# MouseGoggles_Hat-1-9.net
KiCad netlist of a schematic drawn in EAGLE
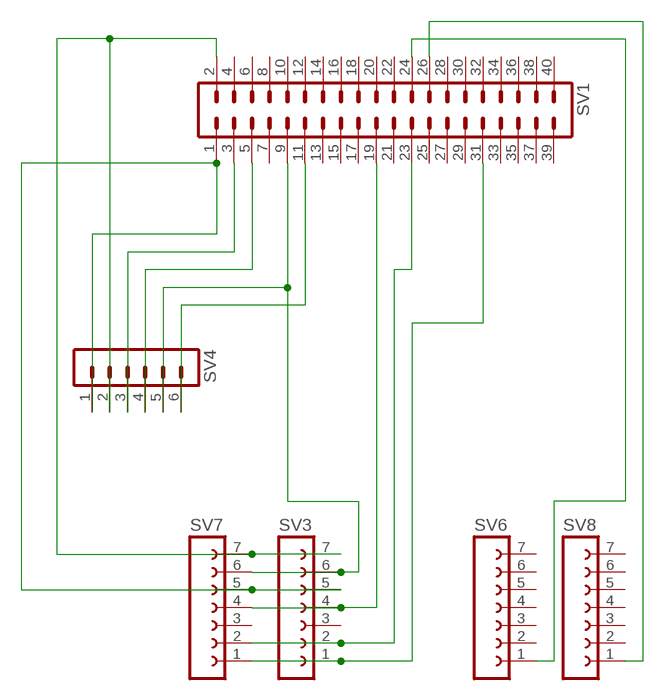
[diagram p0: schematic, sheet 1]

(export (version "E")
  (design (tool "Eeschema 10.0.6"))
  (components
    (comp (ref "SV1")
      (value "MA20-2")
      (footprint "eagle-import:MA20-2")
      (libsource (lib "eagle-import") (part "MA20-2"))
    )
    (comp (ref "SV3")
      (value "FE07-1")
      (footprint "eagle-import:FE07")
      (libsource (lib "eagle-import") (part "FE07-1"))
    )
    (comp (ref "SV4")
      (value "MA06-1")
      (footprint "eagle-import:MA06-1")
      (libsource (lib "eagle-import") (part "MA06-1"))
    )
    (comp (ref "SV6")
      (value "FE07-1")
      (footprint "eagle-import:FE07")
      (libsource (lib "eagle-import") (part "FE07-1"))
    )
    (comp (ref "SV7")
      (value "FE07-1")
      (footprint "eagle-import:FE07")
      (libsource (lib "eagle-import") (part "FE07-1"))
    )
    (comp (ref "SV8")
      (value "FE07-1")
      (footprint "eagle-import:FE07")
      (libsource (lib "eagle-import") (part "FE07-1"))
    )
  )
  (nets
    (net (code "1") (name "Net-(SV1-Pad1)") (class "Default")
      (node (ref "SV1") (pin "1") (pinfunction "1_1") (pintype "passive"))
      (node (ref "SV3") (pin "5") (pinfunction "5_5") (pintype "passive"))
      (node (ref "SV4") (pin "1") (pinfunction "1_1") (pintype "passive"))
      (node (ref "SV7") (pin "5") (pinfunction "5_5") (pintype "passive"))
    )
    (net (code "2") (name "Net-(SV1-Pad2)") (class "Default")
      (node (ref "SV1") (pin "2") (pinfunction "2_2") (pintype "passive"))
      (node (ref "SV3") (pin "7") (pinfunction "7_7") (pintype "passive"))
      (node (ref "SV4") (pin "2") (pinfunction "2_2") (pintype "passive"))
      (node (ref "SV7") (pin "7") (pinfunction "7_7") (pintype "passive"))
    )
    (net (code "3") (name "Net-(SV1-Pad3)") (class "Default")
      (node (ref "SV1") (pin "3") (pinfunction "3_3") (pintype "passive"))
      (node (ref "SV4") (pin "3") (pinfunction "3_3") (pintype "passive"))
    )
    (net (code "4") (name "Net-(SV1-Pad5)") (class "Default")
      (node (ref "SV1") (pin "5") (pinfunction "5_5") (pintype "passive"))
      (node (ref "SV4") (pin "4") (pinfunction "4_4") (pintype "passive"))
    )
    (net (code "5") (name "Net-(SV1-Pad9)") (class "Default")
      (node (ref "SV1") (pin "9") (pinfunction "9_9") (pintype "passive"))
      (node (ref "SV3") (pin "6") (pinfunction "6_6") (pintype "passive"))
      (node (ref "SV4") (pin "5") (pinfunction "5_5") (pintype "passive"))
      (node (ref "SV7") (pin "6") (pinfunction "6_6") (pintype "passive"))
    )
    (net (code "6") (name "Net-(SV1-Pad11)") (class "Default")
      (node (ref "SV1") (pin "11") (pinfunction "11_11") (pintype "passive"))
      (node (ref "SV4") (pin "6") (pinfunction "6_6") (pintype "passive"))
    )
    (net (code "7") (name "Net-(SV1-Pad19)") (class "Default")
      (node (ref "SV1") (pin "19") (pinfunction "19_19") (pintype "passive"))
      (node (ref "SV3") (pin "4") (pinfunction "4_4") (pintype "passive"))
      (node (ref "SV7") (pin "4") (pinfunction "4_4") (pintype "passive"))
    )
    (net (code "8") (name "Net-(SV1-Pad23)") (class "Default")
      (node (ref "SV1") (pin "23") (pinfunction "23_23") (pintype "passive"))
      (node (ref "SV3") (pin "2") (pinfunction "2_2") (pintype "passive"))
      (node (ref "SV7") (pin "2") (pinfunction "2_2") (pintype "passive"))
    )
    (net (code "9") (name "Net-(SV1-Pad24)") (class "Default")
      (node (ref "SV1") (pin "24") (pinfunction "24_24") (pintype "passive"))
      (node (ref "SV6") (pin "1") (pinfunction "1_1") (pintype "passive"))
    )
    (net (code "10") (name "Net-(SV1-Pad26)") (class "Default")
      (node (ref "SV1") (pin "26") (pinfunction "26_26") (pintype "passive"))
      (node (ref "SV8") (pin "1") (pinfunction "1_1") (pintype "passive"))
    )
    (net (code "11") (name "Net-(SV1-Pad31)") (class "Default")
      (node (ref "SV1") (pin "31") (pinfunction "31_31") (pintype "passive"))
      (node (ref "SV3") (pin "1") (pinfunction "1_1") (pintype "passive"))
      (node (ref "SV7") (pin "1") (pinfunction "1_1") (pintype "passive"))
    )
    (net (code "12") (name "unconnected-(SV1-Pad4)") (class "Default")
      (node (ref "SV1") (pin "4") (pinfunction "4_4") (pintype "passive"))
    )
    (net (code "13") (name "unconnected-(SV1-Pad6)") (class "Default")
      (node (ref "SV1") (pin "6") (pinfunction "6_6") (pintype "passive"))
    )
    (net (code "14") (name "unconnected-(SV1-Pad7)") (class "Default")
      (node (ref "SV1") (pin "7") (pinfunction "7_7") (pintype "passive"))
    )
    (net (code "15") (name "unconnected-(SV1-Pad8)") (class "Default")
      (node (ref "SV1") (pin "8") (pinfunction "8_8") (pintype "passive"))
    )
    (net (code "16") (name "unconnected-(SV1-Pad10)") (class "Default")
      (node (ref "SV1") (pin "10") (pinfunction "10_10") (pintype "passive"))
    )
    (net (code "17") (name "unconnected-(SV1-Pad12)") (class "Default")
      (node (ref "SV1") (pin "12") (pinfunction "12_12") (pintype "passive"))
    )
    (net (code "18") (name "unconnected-(SV1-Pad13)") (class "Default")
      (node (ref "SV1") (pin "13") (pinfunction "13_13") (pintype "passive"))
    )
    (net (code "19") (name "unconnected-(SV1-Pad14)") (class "Default")
      (node (ref "SV1") (pin "14") (pinfunction "14_14") (pintype "passive"))
    )
    (net (code "20") (name "unconnected-(SV1-Pad15)") (class "Default")
      (node (ref "SV1") (pin "15") (pinfunction "15_15") (pintype "passive"))
    )
    (net (code "21") (name "unconnected-(SV1-Pad16)") (class "Default")
      (node (ref "SV1") (pin "16") (pinfunction "16_16") (pintype "passive"))
    )
    (net (code "22") (name "unconnected-(SV1-Pad17)") (class "Default")
      (node (ref "SV1") (pin "17") (pinfunction "17_17") (pintype "passive"))
    )
    (net (code "23") (name "unconnected-(SV1-Pad18)") (class "Default")
      (node (ref "SV1") (pin "18") (pinfunction "18_18") (pintype "passive"))
    )
    (net (code "24") (name "unconnected-(SV1-Pad20)") (class "Default")
      (node (ref "SV1") (pin "20") (pinfunction "20_20") (pintype "passive"))
    )
    (net (code "25") (name "unconnected-(SV1-Pad21)") (class "Default")
      (node (ref "SV1") (pin "21") (pinfunction "21_21") (pintype "passive"))
    )
    (net (code "26") (name "unconnected-(SV1-Pad22)") (class "Default")
      (node (ref "SV1") (pin "22") (pinfunction "22_22") (pintype "passive"))
    )
    (net (code "27") (name "unconnected-(SV1-Pad25)") (class "Default")
      (node (ref "SV1") (pin "25") (pinfunction "25_25") (pintype "passive"))
    )
    (net (code "28") (name "unconnected-(SV1-Pad27)") (class "Default")
      (node (ref "SV1") (pin "27") (pinfunction "27_27") (pintype "passive"))
    )
    (net (code "29") (name "unconnected-(SV1-Pad28)") (class "Default")
      (node (ref "SV1") (pin "28") (pinfunction "28_28") (pintype "passive"))
    )
    (net (code "30") (name "unconnected-(SV1-Pad29)") (class "Default")
      (node (ref "SV1") (pin "29") (pinfunction "29_29") (pintype "passive"))
    )
    (net (code "31") (name "unconnected-(SV1-Pad30)") (class "Default")
      (node (ref "SV1") (pin "30") (pinfunction "30_30") (pintype "passive"))
    )
    (net (code "32") (name "unconnected-(SV1-Pad32)") (class "Default")
      (node (ref "SV1") (pin "32") (pinfunction "32_32") (pintype "passive"))
    )
    (net (code "33") (name "unconnected-(SV1-Pad33)") (class "Default")
      (node (ref "SV1") (pin "33") (pinfunction "33_33") (pintype "passive"))
    )
    (net (code "34") (name "unconnected-(SV1-Pad34)") (class "Default")
      (node (ref "SV1") (pin "34") (pinfunction "34_34") (pintype "passive"))
    )
    (net (code "35") (name "unconnected-(SV1-Pad35)") (class "Default")
      (node (ref "SV1") (pin "35") (pinfunction "35_35") (pintype "passive"))
    )
    (net (code "36") (name "unconnected-(SV1-Pad36)") (class "Default")
      (node (ref "SV1") (pin "36") (pinfunction "36_36") (pintype "passive"))
    )
    (net (code "37") (name "unconnected-(SV1-Pad37)") (class "Default")
      (node (ref "SV1") (pin "37") (pinfunction "37_37") (pintype "passive"))
    )
    (net (code "38") (name "unconnected-(SV1-Pad38)") (class "Default")
      (node (ref "SV1") (pin "38") (pinfunction "38_38") (pintype "passive"))
    )
    (net (code "39") (name "unconnected-(SV1-Pad39)") (class "Default")
      (node (ref "SV1") (pin "39") (pinfunction "39_39") (pintype "passive"))
    )
    (net (code "40") (name "unconnected-(SV1-Pad40)") (class "Default")
      (node (ref "SV1") (pin "40") (pinfunction "40_40") (pintype "passive"))
    )
    (net (code "41") (name "unconnected-(SV3-Pad3)") (class "Default")
      (node (ref "SV3") (pin "3") (pinfunction "3_3") (pintype "passive"))
    )
    (net (code "42") (name "unconnected-(SV6-Pad2)") (class "Default")
      (node (ref "SV6") (pin "2") (pinfunction "2_2") (pintype "passive"))
    )
    (net (code "43") (name "unconnected-(SV6-Pad3)") (class "Default")
      (node (ref "SV6") (pin "3") (pinfunction "3_3") (pintype "passive"))
    )
    (net (code "44") (name "unconnected-(SV6-Pad4)") (class "Default")
      (node (ref "SV6") (pin "4") (pinfunction "4_4") (pintype "passive"))
    )
    (net (code "45") (name "unconnected-(SV6-Pad5)") (class "Default")
      (node (ref "SV6") (pin "5") (pinfunction "5_5") (pintype "passive"))
    )
    (net (code "46") (name "unconnected-(SV6-Pad6)") (class "Default")
      (node (ref "SV6") (pin "6") (pinfunction "6_6") (pintype "passive"))
    )
    (net (code "47") (name "unconnected-(SV6-Pad7)") (class "Default")
      (node (ref "SV6") (pin "7") (pinfunction "7_7") (pintype "passive"))
    )
    (net (code "48") (name "unconnected-(SV7-Pad3)") (class "Default")
      (node (ref "SV7") (pin "3") (pinfunction "3_3") (pintype "passive"))
    )
    (net (code "49") (name "unconnected-(SV8-Pad2)") (class "Default")
      (node (ref "SV8") (pin "2") (pinfunction "2_2") (pintype "passive"))
    )
    (net (code "50") (name "unconnected-(SV8-Pad3)") (class "Default")
      (node (ref "SV8") (pin "3") (pinfunction "3_3") (pintype "passive"))
    )
    (net (code "51") (name "unconnected-(SV8-Pad4)") (class "Default")
      (node (ref "SV8") (pin "4") (pinfunction "4_4") (pintype "passive"))
    )
    (net (code "52") (name "unconnected-(SV8-Pad5)") (class "Default")
      (node (ref "SV8") (pin "5") (pinfunction "5_5") (pintype "passive"))
    )
    (net (code "53") (name "unconnected-(SV8-Pad6)") (class "Default")
      (node (ref "SV8") (pin "6") (pinfunction "6_6") (pintype "passive"))
    )
    (net (code "54") (name "unconnected-(SV8-Pad7)") (class "Default")
      (node (ref "SV8") (pin "7") (pinfunction "7_7") (pintype "passive"))
    )
  )
)
